# Microcontroller.net
KiCad netlist of a schematic drawn in Altium Designer
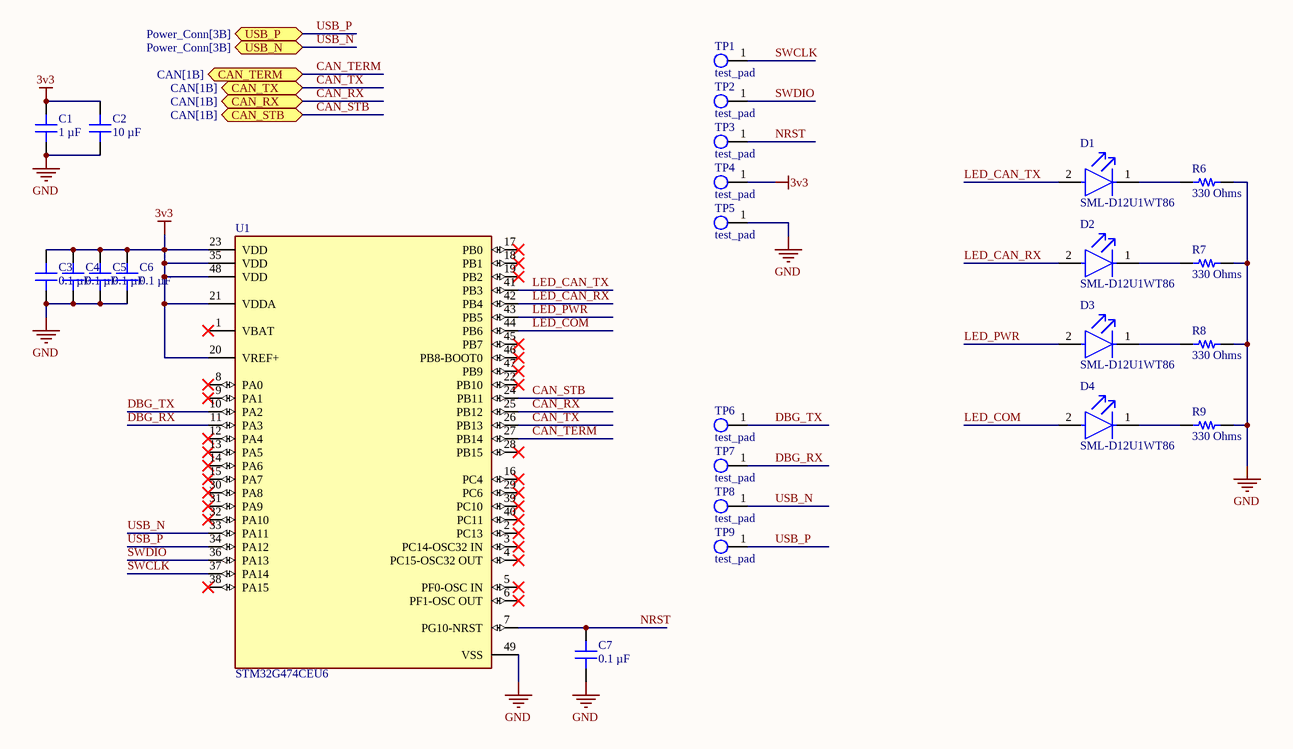
[diagram p0: Microcontroller.SchDoc]

(export (version "E")
  (design (tool "Eeschema 10.0.6"))
  (components
    (comp (ref "C1")
      (value "1 µF")
      (footprint "CAP 0603_1608")
      (description "CAP CER 1UF 10V X7R 0603")
      (fields
        (field (name "PART NUMBER") "CL10B105KP8NFNC")
        (field (name "MANUFACTURER") "Samsung Electro-Mechanics")
      )
      (libsource (lib "Celestial Altium Library - altium_library") (part "Capacitor"))
    )
    (comp (ref "C2")
      (value "10 µF")
      (footprint "CAP 0805_2012")
      (description "CAP CER 10UF 16V X5R 0805")
      (fields
        (field (name "PART NUMBER") "CL21A106KOQNNNE")
        (field (name "MANUFACTURER") "Samsung Electro-Mechanics")
      )
      (libsource (lib "Celestial Altium Library - altium_library") (part "Capacitor"))
    )
    (comp (ref "C3")
      (value "0.1 µF")
      (footprint "CAP 0603_1608")
      (description "CAP CER 0.1UF 50V X7R 0603")
      (fields
        (field (name "PART NUMBER") "CL10B104KB8NNNC")
        (field (name "MANUFACTURER") "Samsung Electro-Mechanics")
      )
      (libsource (lib "Celestial Altium Library - altium_library") (part "Capacitor"))
    )
    (comp (ref "C4")
      (value "0.1 µF")
      (footprint "CAP 0603_1608")
      (description "CAP CER 0.1UF 50V X7R 0603")
      (fields
        (field (name "PART NUMBER") "CL10B104KB8NNNC")
        (field (name "MANUFACTURER") "Samsung Electro-Mechanics")
      )
      (libsource (lib "Celestial Altium Library - altium_library") (part "Capacitor"))
    )
    (comp (ref "C5")
      (value "0.1 µF")
      (footprint "CAP 0603_1608")
      (description "CAP CER 0.1UF 50V X7R 0603")
      (fields
        (field (name "PART NUMBER") "CL10B104KB8NNNC")
        (field (name "MANUFACTURER") "Samsung Electro-Mechanics")
      )
      (libsource (lib "Celestial Altium Library - altium_library") (part "Capacitor"))
    )
    (comp (ref "C6")
      (value "0.1 µF")
      (footprint "CAP 0603_1608")
      (description "CAP CER 0.1UF 50V X7R 0603")
      (fields
        (field (name "PART NUMBER") "CL10B104KB8NNNC")
        (field (name "MANUFACTURER") "Samsung Electro-Mechanics")
      )
      (libsource (lib "Celestial Altium Library - altium_library") (part "Capacitor"))
    )
    (comp (ref "C7")
      (value "0.1 µF")
      (footprint "CAP 0603_1608")
      (description "CAP CER 0.1UF 50V X7R 0603")
      (fields
        (field (name "PART NUMBER") "CL10B104KB8NNNC")
        (field (name "MANUFACTURER") "Samsung Electro-Mechanics")
      )
      (libsource (lib "Celestial Altium Library - altium_library") (part "Capacitor"))
    )
    (comp (ref "D1")
      (value "SML-D12U1WT86")
      (footprint "FP-SML-D12-MFG")
      (description "LED RED DIFFUSED 1608 SMD")
      (fields
        (field (name "MANUFACTURER") "Rohm")
        (field (name "OCTOPART") "https://octopart.com/sml-d12u1wt86-rohm-70850259")
      )
      (libsource (lib "Altium Content Vault") (part "8706943c75ba83719d021d2fdc84c58"))
    )
    (comp (ref "D2")
      (value "SML-D12U1WT86")
      (footprint "FP-SML-D12-MFG")
      (description "LED RED DIFFUSED 1608 SMD")
      (fields
        (field (name "MANUFACTURER") "Rohm")
        (field (name "OCTOPART") "https://octopart.com/sml-d12u1wt86-rohm-70850259")
      )
      (libsource (lib "Altium Content Vault") (part "8706943c75ba83719d021d2fdc84c58"))
    )
    (comp (ref "D3")
      (value "SML-D12U1WT86")
      (footprint "FP-SML-D12-MFG")
      (description "LED RED DIFFUSED 1608 SMD")
      (fields
        (field (name "MANUFACTURER") "Rohm")
        (field (name "OCTOPART") "https://octopart.com/sml-d12u1wt86-rohm-70850259")
      )
      (libsource (lib "Altium Content Vault") (part "8706943c75ba83719d021d2fdc84c58"))
    )
    (comp (ref "D4")
      (value "SML-D12U1WT86")
      (footprint "FP-SML-D12-MFG")
      (description "LED RED DIFFUSED 1608 SMD")
      (fields
        (field (name "MANUFACTURER") "Rohm")
        (field (name "OCTOPART") "https://octopart.com/sml-d12u1wt86-rohm-70850259")
      )
      (libsource (lib "Altium Content Vault") (part "8706943c75ba83719d021d2fdc84c58"))
    )
    (comp (ref "R6")
      (value "330 Ohms")
      (footprint "RES 0603_1608")
      (description "RES SMD 330 OHM 5% 1/10W 0603")
      (fields (field (name "PART NUMBER") "CR0603-JW-331ELF") (field (name "MANUFACTURER") "Bourns Inc."))
      (libsource (lib "Celestial Altium Library - altium_library") (part "Resistor"))
    )
    (comp (ref "R7")
      (value "330 Ohms")
      (footprint "RES 0603_1608")
      (description "RES SMD 330 OHM 5% 1/10W 0603")
      (fields (field (name "PART NUMBER") "CR0603-JW-331ELF") (field (name "MANUFACTURER") "Bourns Inc."))
      (libsource (lib "Celestial Altium Library - altium_library") (part "Resistor"))
    )
    (comp (ref "R8")
      (value "330 Ohms")
      (footprint "RES 0603_1608")
      (description "RES SMD 330 OHM 5% 1/10W 0603")
      (fields (field (name "PART NUMBER") "CR0603-JW-331ELF") (field (name "MANUFACTURER") "Bourns Inc."))
      (libsource (lib "Celestial Altium Library - altium_library") (part "Resistor"))
    )
    (comp (ref "R9")
      (value "330 Ohms")
      (footprint "RES 0603_1608")
      (description "RES SMD 330 OHM 5% 1/10W 0603")
      (fields (field (name "PART NUMBER") "CR0603-JW-331ELF") (field (name "MANUFACTURER") "Bourns Inc."))
      (libsource (lib "Celestial Altium Library - altium_library") (part "Resistor"))
    )
    (comp (ref "TP1")
      (value "test_pad")
      (footprint "2mm TP")
      (description "Test pad for ICT")
      (libsource (lib "2020-09-26_17-27-19") (part "test_pad"))
    )
    (comp (ref "TP2")
      (value "test_pad")
      (footprint "2mm TP")
      (description "Test pad for ICT")
      (libsource (lib "2020-09-26_17-27-19") (part "test_pad"))
    )
    (comp (ref "TP3")
      (value "test_pad")
      (footprint "2mm TP")
      (description "Test pad for ICT")
      (libsource (lib "2020-09-26_17-27-19") (part "test_pad"))
    )
    (comp (ref "TP4")
      (value "test_pad")
      (footprint "2mm TP")
      (description "Test pad for ICT")
      (libsource (lib "2020-09-26_17-27-19") (part "test_pad"))
    )
    (comp (ref "TP5")
      (value "test_pad")
      (footprint "2mm TP")
      (description "Test pad for ICT")
      (libsource (lib "2020-09-26_17-27-19") (part "test_pad"))
    )
    (comp (ref "TP6")
      (value "test_pad")
      (footprint "2mm TP")
      (description "Test pad for ICT")
      (libsource (lib "2020-09-26_17-27-19") (part "test_pad"))
    )
    (comp (ref "TP7")
      (value "test_pad")
      (footprint "2mm TP")
      (description "Test pad for ICT")
      (libsource (lib "2020-09-26_17-27-19") (part "test_pad"))
    )
    (comp (ref "TP8")
      (value "test_pad")
      (footprint "2mm TP")
      (description "Test pad for ICT")
      (libsource (lib "2020-09-26_17-27-19") (part "test_pad"))
    )
    (comp (ref "TP9")
      (value "test_pad")
      (footprint "2mm TP")
      (description "Test pad for ICT")
      (libsource (lib "2020-09-26_17-27-19") (part "test_pad"))
    )
    (comp (ref "U1")
      (value "STM32G474CEU6")
      (footprint "FP-UFQFPN48-A0B9-IPC_C")
      (description "MAINSTREAM ARM CORTEX-M4 CORE WI")
      (libsource (lib "Altium Content Vault") (part "b3691d769e225857764b15fce0dd265"))
    )
  )
  (nets
    (net (code "1") (name "/CAN_RX") (class "Default")
      (node (ref "U1") (pin "25") (pinfunction "PB12_25") (pintype "bidirectional"))
    )
    (net (code "2") (name "/CAN_STB") (class "Default")
      (node (ref "U1") (pin "24") (pinfunction "PB11_24") (pintype "bidirectional"))
    )
    (net (code "3") (name "/CAN_TERM") (class "Default")
      (node (ref "U1") (pin "27") (pinfunction "PB14_27") (pintype "bidirectional"))
    )
    (net (code "4") (name "/CAN_TX") (class "Default")
      (node (ref "U1") (pin "26") (pinfunction "PB13_26") (pintype "bidirectional"))
    )
    (net (code "5") (name "/DBG_RX") (class "Default")
      (node (ref "TP7") (pin "1") (pintype "passive"))
      (node (ref "U1") (pin "11") (pinfunction "PA3_11") (pintype "bidirectional"))
    )
    (net (code "6") (name "/DBG_TX") (class "Default")
      (node (ref "TP6") (pin "1") (pintype "passive"))
      (node (ref "U1") (pin "10") (pinfunction "PA2_10") (pintype "bidirectional"))
    )
    (net (code "7") (name "/LED_CAN_RX") (class "Default")
      (node (ref "D2") (pin "2") (pinfunction "A_2") (pintype "passive"))
      (node (ref "U1") (pin "42") (pinfunction "PB4_42") (pintype "bidirectional"))
    )
    (net (code "8") (name "/LED_CAN_TX") (class "Default")
      (node (ref "D1") (pin "2") (pinfunction "A_2") (pintype "passive"))
      (node (ref "U1") (pin "41") (pinfunction "PB3_41") (pintype "bidirectional"))
    )
    (net (code "9") (name "/LED_COM") (class "Default")
      (node (ref "D4") (pin "2") (pinfunction "A_2") (pintype "passive"))
      (node (ref "U1") (pin "44") (pinfunction "PB6_44") (pintype "bidirectional"))
    )
    (net (code "10") (name "/LED_PWR") (class "Default")
      (node (ref "D3") (pin "2") (pinfunction "A_2") (pintype "passive"))
      (node (ref "U1") (pin "43") (pinfunction "PB5_43") (pintype "bidirectional"))
    )
    (net (code "11") (name "/NRST") (class "Default")
      (node (ref "C7") (pin "2") (pinfunction "2_2") (pintype "passive"))
      (node (ref "TP3") (pin "1") (pintype "passive"))
      (node (ref "U1") (pin "7") (pinfunction "PG10-NRST_7") (pintype "bidirectional"))
    )
    (net (code "12") (name "/SWCLK") (class "Default")
      (node (ref "TP1") (pin "1") (pintype "passive"))
      (node (ref "U1") (pin "37") (pinfunction "PA14_37") (pintype "bidirectional"))
    )
    (net (code "13") (name "/SWDIO") (class "Default")
      (node (ref "TP2") (pin "1") (pintype "passive"))
      (node (ref "U1") (pin "36") (pinfunction "PA13_36") (pintype "bidirectional"))
    )
    (net (code "14") (name "/USB_N") (class "Default")
      (node (ref "TP8") (pin "1") (pintype "passive"))
      (node (ref "U1") (pin "33") (pinfunction "PA11_33") (pintype "bidirectional"))
    )
    (net (code "15") (name "/USB_P") (class "Default")
      (node (ref "TP9") (pin "1") (pintype "passive"))
      (node (ref "U1") (pin "34") (pinfunction "PA12_34") (pintype "bidirectional"))
    )
    (net (code "16") (name "3v3") (class "Default")
      (node (ref "C1") (pin "2") (pinfunction "2_2") (pintype "passive"))
      (node (ref "C2") (pin "2") (pinfunction "2_2") (pintype "passive"))
      (node (ref "C3") (pin "2") (pinfunction "2_2") (pintype "passive"))
      (node (ref "C4") (pin "2") (pinfunction "2_2") (pintype "passive"))
      (node (ref "C5") (pin "2") (pinfunction "2_2") (pintype "passive"))
      (node (ref "C6") (pin "2") (pinfunction "2_2") (pintype "passive"))
      (node (ref "TP4") (pin "1") (pintype "passive"))
      (node (ref "U1") (pin "20") (pinfunction "VREF+_20") (pintype "power_in"))
      (node (ref "U1") (pin "21") (pinfunction "VDDA_21") (pintype "power_in"))
      (node (ref "U1") (pin "23") (pinfunction "VDD_23") (pintype "power_in"))
      (node (ref "U1") (pin "35") (pinfunction "VDD_35") (pintype "power_in"))
      (node (ref "U1") (pin "48") (pinfunction "VDD_48") (pintype "power_in"))
    )
    (net (code "17") (name "GND") (class "Default")
      (node (ref "C1") (pin "1") (pinfunction "1_1") (pintype "passive"))
      (node (ref "C2") (pin "1") (pinfunction "1_1") (pintype "passive"))
      (node (ref "C3") (pin "1") (pinfunction "1_1") (pintype "passive"))
      (node (ref "C4") (pin "1") (pinfunction "1_1") (pintype "passive"))
      (node (ref "C5") (pin "1") (pinfunction "1_1") (pintype "passive"))
      (node (ref "C6") (pin "1") (pinfunction "1_1") (pintype "passive"))
      (node (ref "C7") (pin "1") (pinfunction "1_1") (pintype "passive"))
      (node (ref "R6") (pin "1") (pinfunction "1_1") (pintype "passive"))
      (node (ref "R7") (pin "1") (pinfunction "1_1") (pintype "passive"))
      (node (ref "R8") (pin "1") (pinfunction "1_1") (pintype "passive"))
      (node (ref "R9") (pin "1") (pinfunction "1_1") (pintype "passive"))
      (node (ref "TP5") (pin "1") (pintype "passive"))
      (node (ref "U1") (pin "49") (pinfunction "VSS_49") (pintype "power_in"))
    )
    (net (code "18") (name "Net-(D1-C)") (class "Default")
      (node (ref "D1") (pin "1") (pinfunction "C_1") (pintype "passive"))
      (node (ref "R6") (pin "2") (pinfunction "2_2") (pintype "passive"))
    )
    (net (code "19") (name "Net-(D2-C)") (class "Default")
      (node (ref "D2") (pin "1") (pinfunction "C_1") (pintype "passive"))
      (node (ref "R7") (pin "2") (pinfunction "2_2") (pintype "passive"))
    )
    (net (code "20") (name "Net-(D3-C)") (class "Default")
      (node (ref "D3") (pin "1") (pinfunction "C_1") (pintype "passive"))
      (node (ref "R8") (pin "2") (pinfunction "2_2") (pintype "passive"))
    )
    (net (code "21") (name "Net-(D4-C)") (class "Default")
      (node (ref "D4") (pin "1") (pinfunction "C_1") (pintype "passive"))
      (node (ref "R9") (pin "2") (pinfunction "2_2") (pintype "passive"))
    )
    (net (code "22") (name "unconnected-(U1-PA0-Pad8)") (class "Default")
      (node (ref "U1") (pin "8") (pinfunction "PA0_8") (pintype "bidirectional+no_connect"))
    )
    (net (code "23") (name "unconnected-(U1-PA1-Pad9)") (class "Default")
      (node (ref "U1") (pin "9") (pinfunction "PA1_9") (pintype "bidirectional+no_connect"))
    )
    (net (code "24") (name "unconnected-(U1-PA4-Pad12)") (class "Default")
      (node (ref "U1") (pin "12") (pinfunction "PA4_12") (pintype "bidirectional+no_connect"))
    )
    (net (code "25") (name "unconnected-(U1-PA5-Pad13)") (class "Default")
      (node (ref "U1") (pin "13") (pinfunction "PA5_13") (pintype "bidirectional+no_connect"))
    )
    (net (code "26") (name "unconnected-(U1-PA6-Pad14)") (class "Default")
      (node (ref "U1") (pin "14") (pinfunction "PA6_14") (pintype "bidirectional+no_connect"))
    )
    (net (code "27") (name "unconnected-(U1-PA7-Pad15)") (class "Default")
      (node (ref "U1") (pin "15") (pinfunction "PA7_15") (pintype "bidirectional+no_connect"))
    )
    (net (code "28") (name "unconnected-(U1-PA8-Pad30)") (class "Default")
      (node (ref "U1") (pin "30") (pinfunction "PA8_30") (pintype "bidirectional+no_connect"))
    )
    (net (code "29") (name "unconnected-(U1-PA9-Pad31)") (class "Default")
      (node (ref "U1") (pin "31") (pinfunction "PA9_31") (pintype "bidirectional+no_connect"))
    )
    (net (code "30") (name "unconnected-(U1-PA10-Pad32)") (class "Default")
      (node (ref "U1") (pin "32") (pinfunction "PA10_32") (pintype "bidirectional+no_connect"))
    )
    (net (code "31") (name "unconnected-(U1-PA15-Pad38)") (class "Default")
      (node (ref "U1") (pin "38") (pinfunction "PA15_38") (pintype "bidirectional+no_connect"))
    )
    (net (code "32") (name "unconnected-(U1-PB0-Pad17)") (class "Default")
      (node (ref "U1") (pin "17") (pinfunction "PB0_17") (pintype "bidirectional+no_connect"))
    )
    (net (code "33") (name "unconnected-(U1-PB1-Pad18)") (class "Default")
      (node (ref "U1") (pin "18") (pinfunction "PB1_18") (pintype "bidirectional+no_connect"))
    )
    (net (code "34") (name "unconnected-(U1-PB2-Pad19)") (class "Default")
      (node (ref "U1") (pin "19") (pinfunction "PB2_19") (pintype "bidirectional+no_connect"))
    )
    (net (code "35") (name "unconnected-(U1-PB7-Pad45)") (class "Default")
      (node (ref "U1") (pin "45") (pinfunction "PB7_45") (pintype "bidirectional+no_connect"))
    )
    (net (code "36") (name "unconnected-(U1-PB8-BOOT0-Pad46)") (class "Default")
      (node (ref "U1") (pin "46") (pinfunction "PB8-BOOT0_46") (pintype "bidirectional+no_connect"))
    )
    (net (code "37") (name "unconnected-(U1-PB9-Pad47)") (class "Default")
      (node (ref "U1") (pin "47") (pinfunction "PB9_47") (pintype "bidirectional+no_connect"))
    )
    (net (code "38") (name "unconnected-(U1-PB10-Pad22)") (class "Default")
      (node (ref "U1") (pin "22") (pinfunction "PB10_22") (pintype "bidirectional+no_connect"))
    )
    (net (code "39") (name "unconnected-(U1-PB15-Pad28)") (class "Default")
      (node (ref "U1") (pin "28") (pinfunction "PB15_28") (pintype "bidirectional+no_connect"))
    )
    (net (code "40") (name "unconnected-(U1-PC4-Pad16)") (class "Default")
      (node (ref "U1") (pin "16") (pinfunction "PC4_16") (pintype "bidirectional+no_connect"))
    )
    (net (code "41") (name "unconnected-(U1-PC6-Pad29)") (class "Default")
      (node (ref "U1") (pin "29") (pinfunction "PC6_29") (pintype "bidirectional+no_connect"))
    )
    (net (code "42") (name "unconnected-(U1-PC10-Pad39)") (class "Default")
      (node (ref "U1") (pin "39") (pinfunction "PC10_39") (pintype "bidirectional+no_connect"))
    )
    (net (code "43") (name "unconnected-(U1-PC11-Pad40)") (class "Default")
      (node (ref "U1") (pin "40") (pinfunction "PC11_40") (pintype "bidirectional+no_connect"))
    )
    (net (code "44") (name "unconnected-(U1-PC13-Pad2)") (class "Default")
      (node (ref "U1") (pin "2") (pinfunction "PC13_2") (pintype "bidirectional+no_connect"))
    )
    (net (code "45") (name "unconnected-(U1-PC14-OSC32_IN-Pad3)") (class "Default")
      (node (ref "U1") (pin "3") (pinfunction "PC14-OSC32_IN_3") (pintype "bidirectional+no_connect"))
    )
    (net (code "46") (name "unconnected-(U1-PC15-OSC32_OUT-Pad4)") (class "Default")
      (node (ref "U1") (pin "4") (pinfunction "PC15-OSC32_OUT_4") (pintype "bidirectional+no_connect"))
    )
    (net (code "47") (name "unconnected-(U1-PF0-OSC_IN-Pad5)") (class "Default")
      (node (ref "U1") (pin "5") (pinfunction "PF0-OSC_IN_5") (pintype "bidirectional+no_connect"))
    )
    (net (code "48") (name "unconnected-(U1-PF1-OSC_OUT-Pad6)") (class "Default")
      (node (ref "U1") (pin "6") (pinfunction "PF1-OSC_OUT_6") (pintype "bidirectional+no_connect"))
    )
    (net (code "49") (name "unconnected-(U1-VBAT-Pad1)") (class "Default")
      (node (ref "U1") (pin "1") (pinfunction "VBAT_1") (pintype "power_in+no_connect"))
    )
  )
)
